# GameBoy-DMG-Buttons.net
KiCad netlist of a schematic drawn in EAGLE
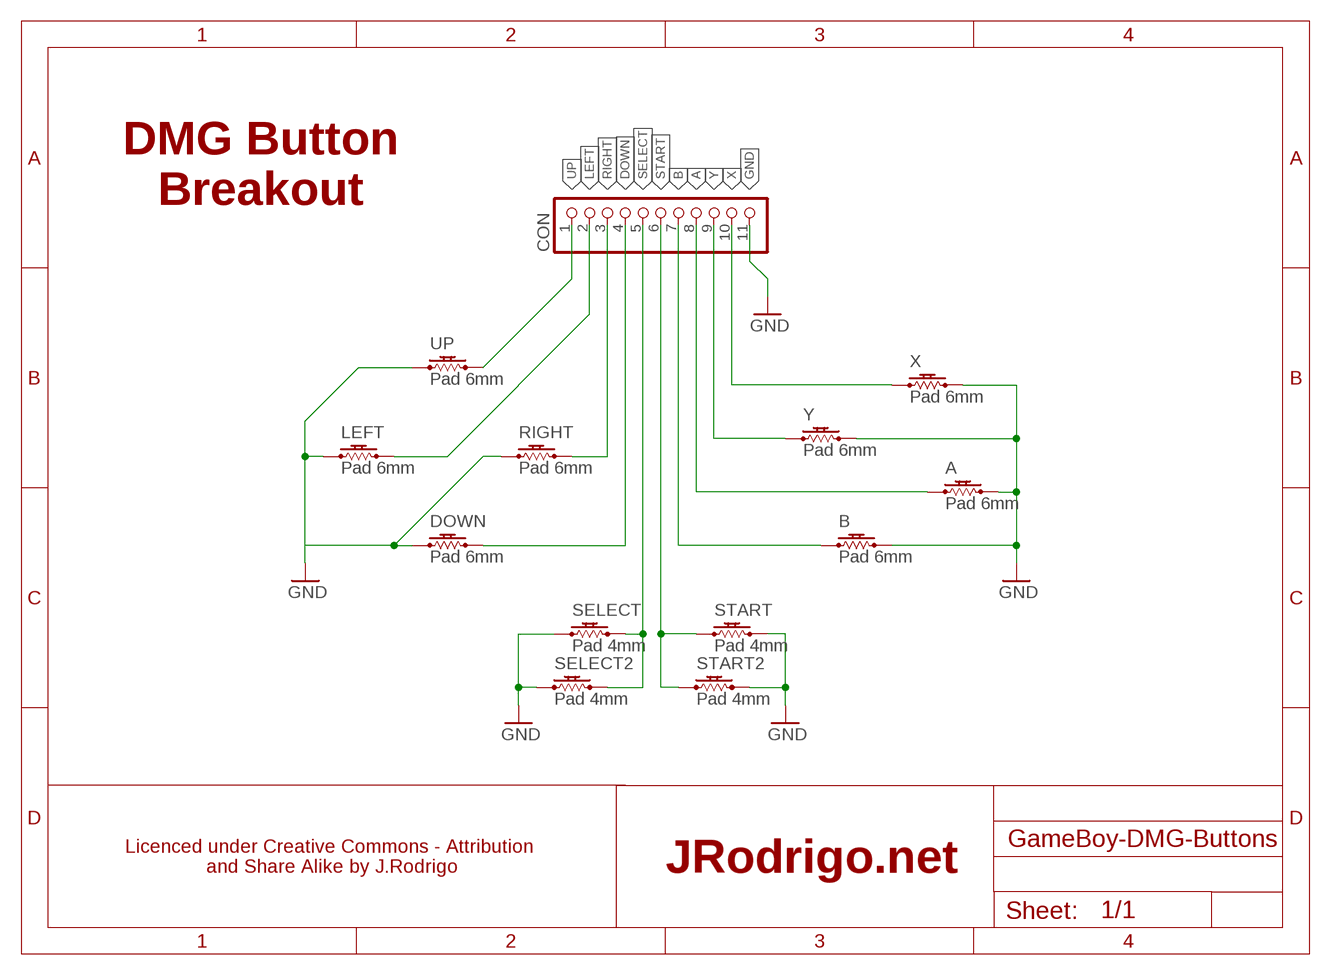
[diagram p0: schematic, sheet 1]

(export (version "E")
  (design (tool "Eeschema 10.0.6"))
  (components
    (comp (ref "A")
      (value "Pad 6mm")
      (footprint "eagle-import:BUTTON_PAD-D6MM")
      (libsource (lib "eagle-import") (part "BUTTON_PAD_6MM"))
    )
    (comp (ref "B")
      (value "Pad 6mm")
      (footprint "eagle-import:BUTTON_PAD-D6MM")
      (libsource (lib "eagle-import") (part "BUTTON_PAD_6MM"))
    )
    (comp (ref "CON")
      (value "PINHD-1X11")
      (footprint "eagle-import:1X11")
      (libsource (lib "eagle-import") (part "PINHD-1X11"))
    )
    (comp (ref "DOWN")
      (value "Pad 6mm")
      (footprint "eagle-import:BUTTON_PAD-D6MM")
      (libsource (lib "eagle-import") (part "BUTTON_PAD_6MM"))
    )
    (comp (ref "LEFT")
      (value "Pad 6mm")
      (footprint "eagle-import:BUTTON_PAD-D6MM")
      (libsource (lib "eagle-import") (part "BUTTON_PAD_6MM"))
    )
    (comp (ref "RIGHT")
      (value "Pad 6mm")
      (footprint "eagle-import:BUTTON_PAD-D6MM")
      (libsource (lib "eagle-import") (part "BUTTON_PAD_6MM"))
    )
    (comp (ref "SELECT")
      (value "Pad 4mm")
      (footprint "eagle-import:BUTTON_PAD-D4MM")
      (libsource (lib "eagle-import") (part "BUTTON_PAD_4MM"))
    )
    (comp (ref "SELECT2")
      (value "Pad 4mm")
      (footprint "eagle-import:BUTTON_PAD-D4MM")
      (libsource (lib "eagle-import") (part "BUTTON_PAD_4MM"))
    )
    (comp (ref "START")
      (value "Pad 4mm")
      (footprint "eagle-import:BUTTON_PAD-D4MM")
      (libsource (lib "eagle-import") (part "BUTTON_PAD_4MM"))
    )
    (comp (ref "START2")
      (value "Pad 4mm")
      (footprint "eagle-import:BUTTON_PAD-D4MM")
      (libsource (lib "eagle-import") (part "BUTTON_PAD_4MM"))
    )
    (comp (ref "UP")
      (value "Pad 6mm")
      (footprint "eagle-import:BUTTON_PAD-D6MM")
      (libsource (lib "eagle-import") (part "BUTTON_PAD_6MM"))
    )
    (comp (ref "X")
      (value "Pad 6mm")
      (footprint "eagle-import:BUTTON_PAD-D6MM")
      (libsource (lib "eagle-import") (part "BUTTON_PAD_6MM"))
    )
    (comp (ref "Y")
      (value "Pad 6mm")
      (footprint "eagle-import:BUTTON_PAD-D6MM")
      (libsource (lib "eagle-import") (part "BUTTON_PAD_6MM"))
    )
  )
  (nets
    (net (code "1") (name "A") (class "Default")
      (node (ref "A") (pin "P1") (pinfunction "1_P1") (pintype "passive"))
      (node (ref "CON") (pin "8") (pinfunction "8_8") (pintype "passive"))
    )
    (net (code "2") (name "B") (class "Default")
      (node (ref "B") (pin "P1") (pinfunction "1_P1") (pintype "passive"))
      (node (ref "CON") (pin "7") (pinfunction "7_7") (pintype "passive"))
    )
    (net (code "3") (name "DOWN") (class "Default")
      (node (ref "CON") (pin "4") (pinfunction "4_4") (pintype "passive"))
      (node (ref "DOWN") (pin "P2") (pinfunction "2_P2") (pintype "passive"))
    )
    (net (code "4") (name "GND") (class "Default")
      (node (ref "A") (pin "P2") (pinfunction "2_P2") (pintype "passive"))
      (node (ref "B") (pin "P2") (pinfunction "2_P2") (pintype "passive"))
      (node (ref "CON") (pin "11") (pinfunction "11_11") (pintype "passive"))
      (node (ref "DOWN") (pin "P1") (pinfunction "1_P1") (pintype "passive"))
      (node (ref "LEFT") (pin "P1") (pinfunction "1_P1") (pintype "passive"))
      (node (ref "RIGHT") (pin "P1") (pinfunction "1_P1") (pintype "passive"))
      (node (ref "SELECT") (pin "P1") (pinfunction "1_P1") (pintype "passive"))
      (node (ref "SELECT2") (pin "P1") (pinfunction "1_P1") (pintype "passive"))
      (node (ref "START") (pin "P2") (pinfunction "2_P2") (pintype "passive"))
      (node (ref "START2") (pin "P2") (pinfunction "2_P2") (pintype "passive"))
      (node (ref "UP") (pin "P1") (pinfunction "1_P1") (pintype "passive"))
      (node (ref "X") (pin "P2") (pinfunction "2_P2") (pintype "passive"))
      (node (ref "Y") (pin "P2") (pinfunction "2_P2") (pintype "passive"))
    )
    (net (code "5") (name "LEFT") (class "Default")
      (node (ref "CON") (pin "2") (pinfunction "2_2") (pintype "passive"))
      (node (ref "LEFT") (pin "P2") (pinfunction "2_P2") (pintype "passive"))
    )
    (net (code "6") (name "RIGHT") (class "Default")
      (node (ref "CON") (pin "3") (pinfunction "3_3") (pintype "passive"))
      (node (ref "RIGHT") (pin "P2") (pinfunction "2_P2") (pintype "passive"))
    )
    (net (code "7") (name "SELECT") (class "Default")
      (node (ref "CON") (pin "5") (pinfunction "5_5") (pintype "passive"))
      (node (ref "SELECT") (pin "P2") (pinfunction "2_P2") (pintype "passive"))
      (node (ref "SELECT2") (pin "P2") (pinfunction "2_P2") (pintype "passive"))
    )
    (net (code "8") (name "START") (class "Default")
      (node (ref "CON") (pin "6") (pinfunction "6_6") (pintype "passive"))
      (node (ref "START") (pin "P1") (pinfunction "1_P1") (pintype "passive"))
      (node (ref "START2") (pin "P1") (pinfunction "1_P1") (pintype "passive"))
    )
    (net (code "9") (name "UP") (class "Default")
      (node (ref "CON") (pin "1") (pinfunction "1_1") (pintype "passive"))
      (node (ref "UP") (pin "P2") (pinfunction "2_P2") (pintype "passive"))
    )
    (net (code "10") (name "X") (class "Default")
      (node (ref "CON") (pin "10") (pinfunction "10_10") (pintype "passive"))
      (node (ref "X") (pin "P1") (pinfunction "1_P1") (pintype "passive"))
    )
    (net (code "11") (name "Y") (class "Default")
      (node (ref "CON") (pin "9") (pinfunction "9_9") (pintype "passive"))
      (node (ref "Y") (pin "P1") (pinfunction "1_P1") (pintype "passive"))
    )
  )
)
